# PCB_PCB_NFC-Business-Card1_2025-01-03.net
KiCad netlist of a schematic drawn in EasyEDA
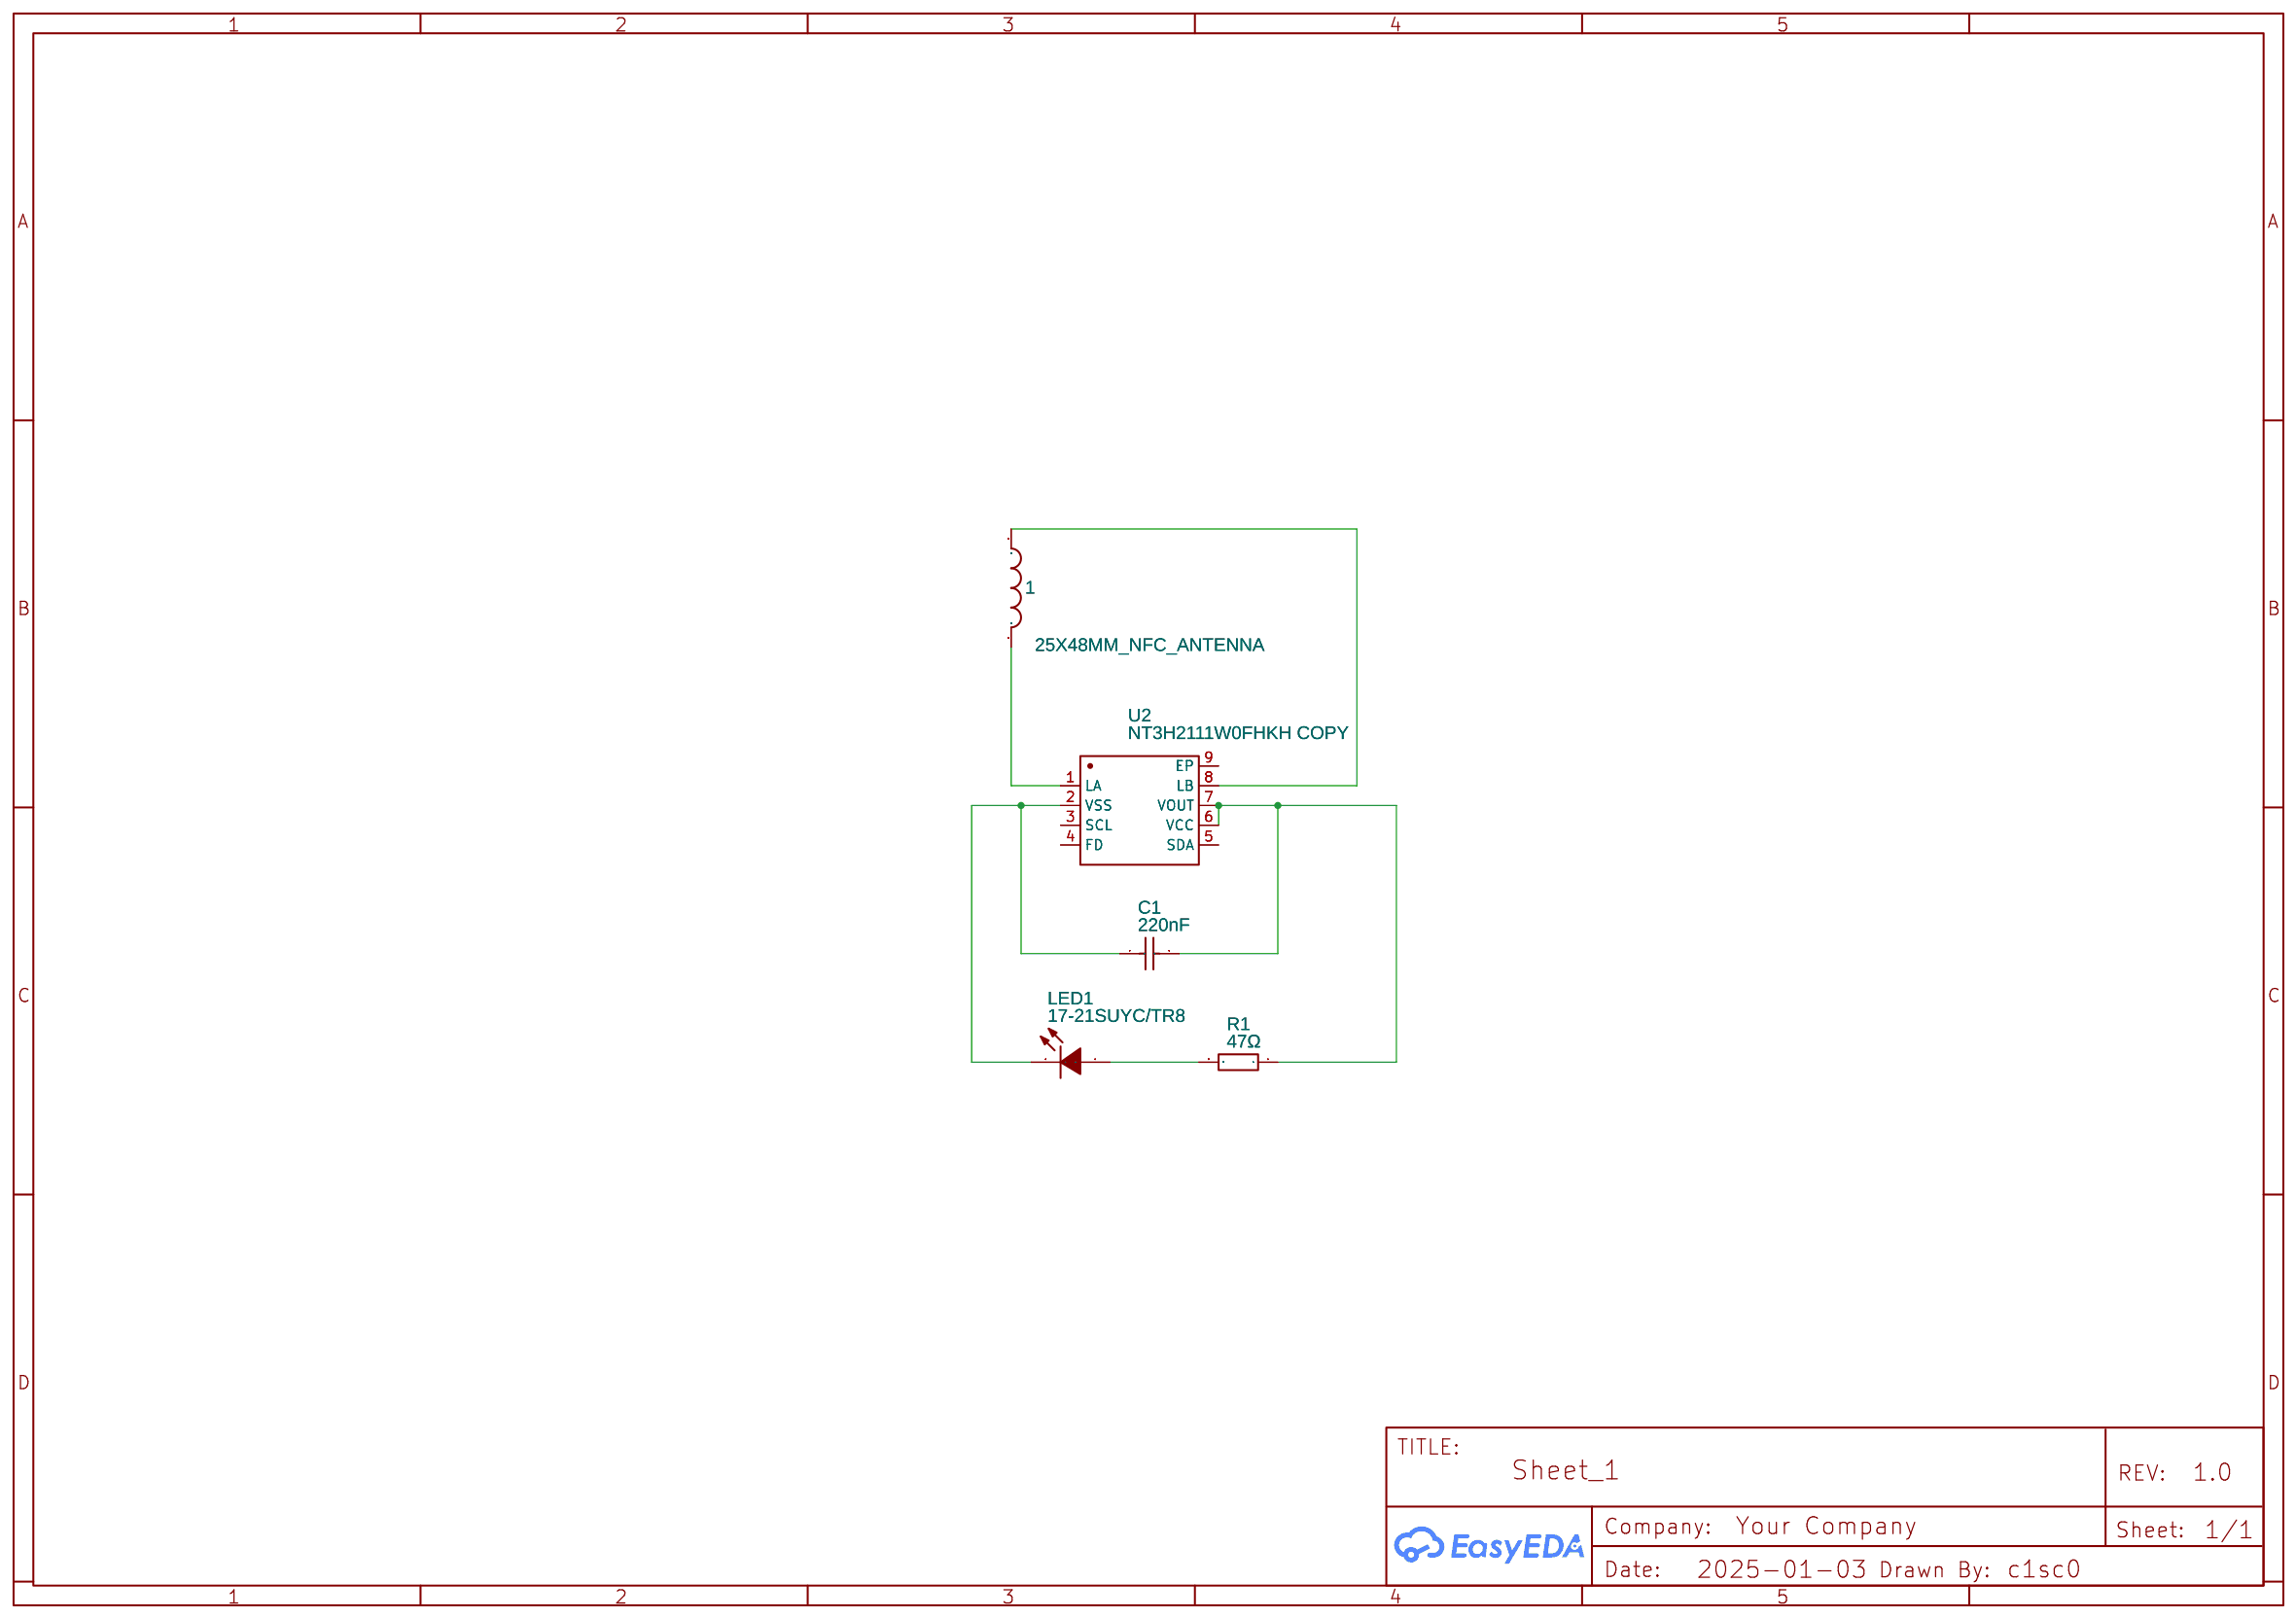
[diagram p0: schematic sheet]

(export (version "E")
  (design (tool "Eeschema 10.0.6"))
  (components
    (comp (ref "1") (value "25X48MM_NFC_ANTENNA") (libsource (lib "") (part "25X48MM_NFC_ANTENNA")))
    (comp (ref "C1")
      (value "220nF")
      (fields
        (field (name "Manufacturer Part") "CL10B224KA8NNNC")
        (field (name "Manufacturer") "SAMSUNG(三星)")
      )
      (libsource (lib "") (part "CL10B224KA8NNNC"))
    )
    (comp (ref "LED1")
      (value "17-21SUYC/TR8")
      (fields (field (name "Manufacturer Part") "KT-0805黄灯") (field (name "Manufacturer") "KENTO"))
      (libsource (lib "") (part "17-21SUYC/TR8"))
    )
    (comp (ref "R1")
      (value "47Ω")
      (fields
        (field (name "Manufacturer Part") "0603WAF470JT5E")
        (field (name "Manufacturer") "UNI-ROYAL(厚声)")
      )
      (libsource (lib "") (part "0603WAF470JT5E"))
    )
    (comp (ref "U2")
      (value "NT3H2111W0FHKH COPY")
      (fields (field (name "Manufacturer Part") "NT3H2111W0FHKH") (field (name "Manufacturer") "NXP(恩智浦)"))
      (libsource (lib "") (part "NT3H2111W0FHKH COPY"))
    )
  )
  (nets
    (net (code "1") (name "Net-(LED1-+)") (class "Default")
      (node (ref "LED1") (pin "1") (pinfunction "+_1") (pintype "unspecified"))
      (node (ref "R1") (pin "2") (pinfunction "2_2") (pintype "input"))
    )
    (net (code "2") (name "Net-(LED1--)") (class "Default")
      (node (ref "C1") (pin "1") (pinfunction "1_1") (pintype "input"))
      (node (ref "LED1") (pin "2") (pinfunction "-_2") (pintype "unspecified"))
      (node (ref "U2") (pin "2") (pinfunction "VSS_2") (pintype "unspecified"))
    )
    (net (code "3") (name "Net-(U2-LA)") (class "Default")
      (node (ref "1") (pin "P$2") (pinfunction "P$2_P$2") (pintype "bidirectional"))
      (node (ref "U2") (pin "1") (pinfunction "LA_1") (pintype "unspecified"))
    )
    (net (code "4") (name "Net-(U2-LB)") (class "Default")
      (node (ref "1") (pin "P$1") (pinfunction "P$1_P$1") (pintype "bidirectional"))
      (node (ref "U2") (pin "8") (pinfunction "LB_8") (pintype "unspecified"))
    )
    (net (code "5") (name "Net-(U2-VCC)") (class "Default")
      (node (ref "C1") (pin "2") (pinfunction "2_2") (pintype "input"))
      (node (ref "R1") (pin "1") (pinfunction "1_1") (pintype "input"))
      (node (ref "U2") (pin "6") (pinfunction "VCC_6") (pintype "unspecified"))
      (node (ref "U2") (pin "7") (pinfunction "VOUT_7") (pintype "unspecified"))
    )
    (net (code "6") (name "unconnected-(U2-EP-Pad9)") (class "Default")
      (node (ref "U2") (pin "9") (pinfunction "EP_9") (pintype "unspecified"))
    )
    (net (code "7") (name "unconnected-(U2-FD-Pad4)") (class "Default")
      (node (ref "U2") (pin "4") (pinfunction "FD_4") (pintype "unspecified"))
    )
    (net (code "8") (name "unconnected-(U2-SCL-Pad3)") (class "Default")
      (node (ref "U2") (pin "3") (pinfunction "SCL_3") (pintype "unspecified"))
    )
    (net (code "9") (name "unconnected-(U2-SDA-Pad5)") (class "Default")
      (node (ref "U2") (pin "5") (pinfunction "SDA_5") (pintype "unspecified"))
    )
  )
)
